# Adafruit_3_5in_480x320_FeatherWing.net
KiCad netlist of a schematic drawn in EAGLE
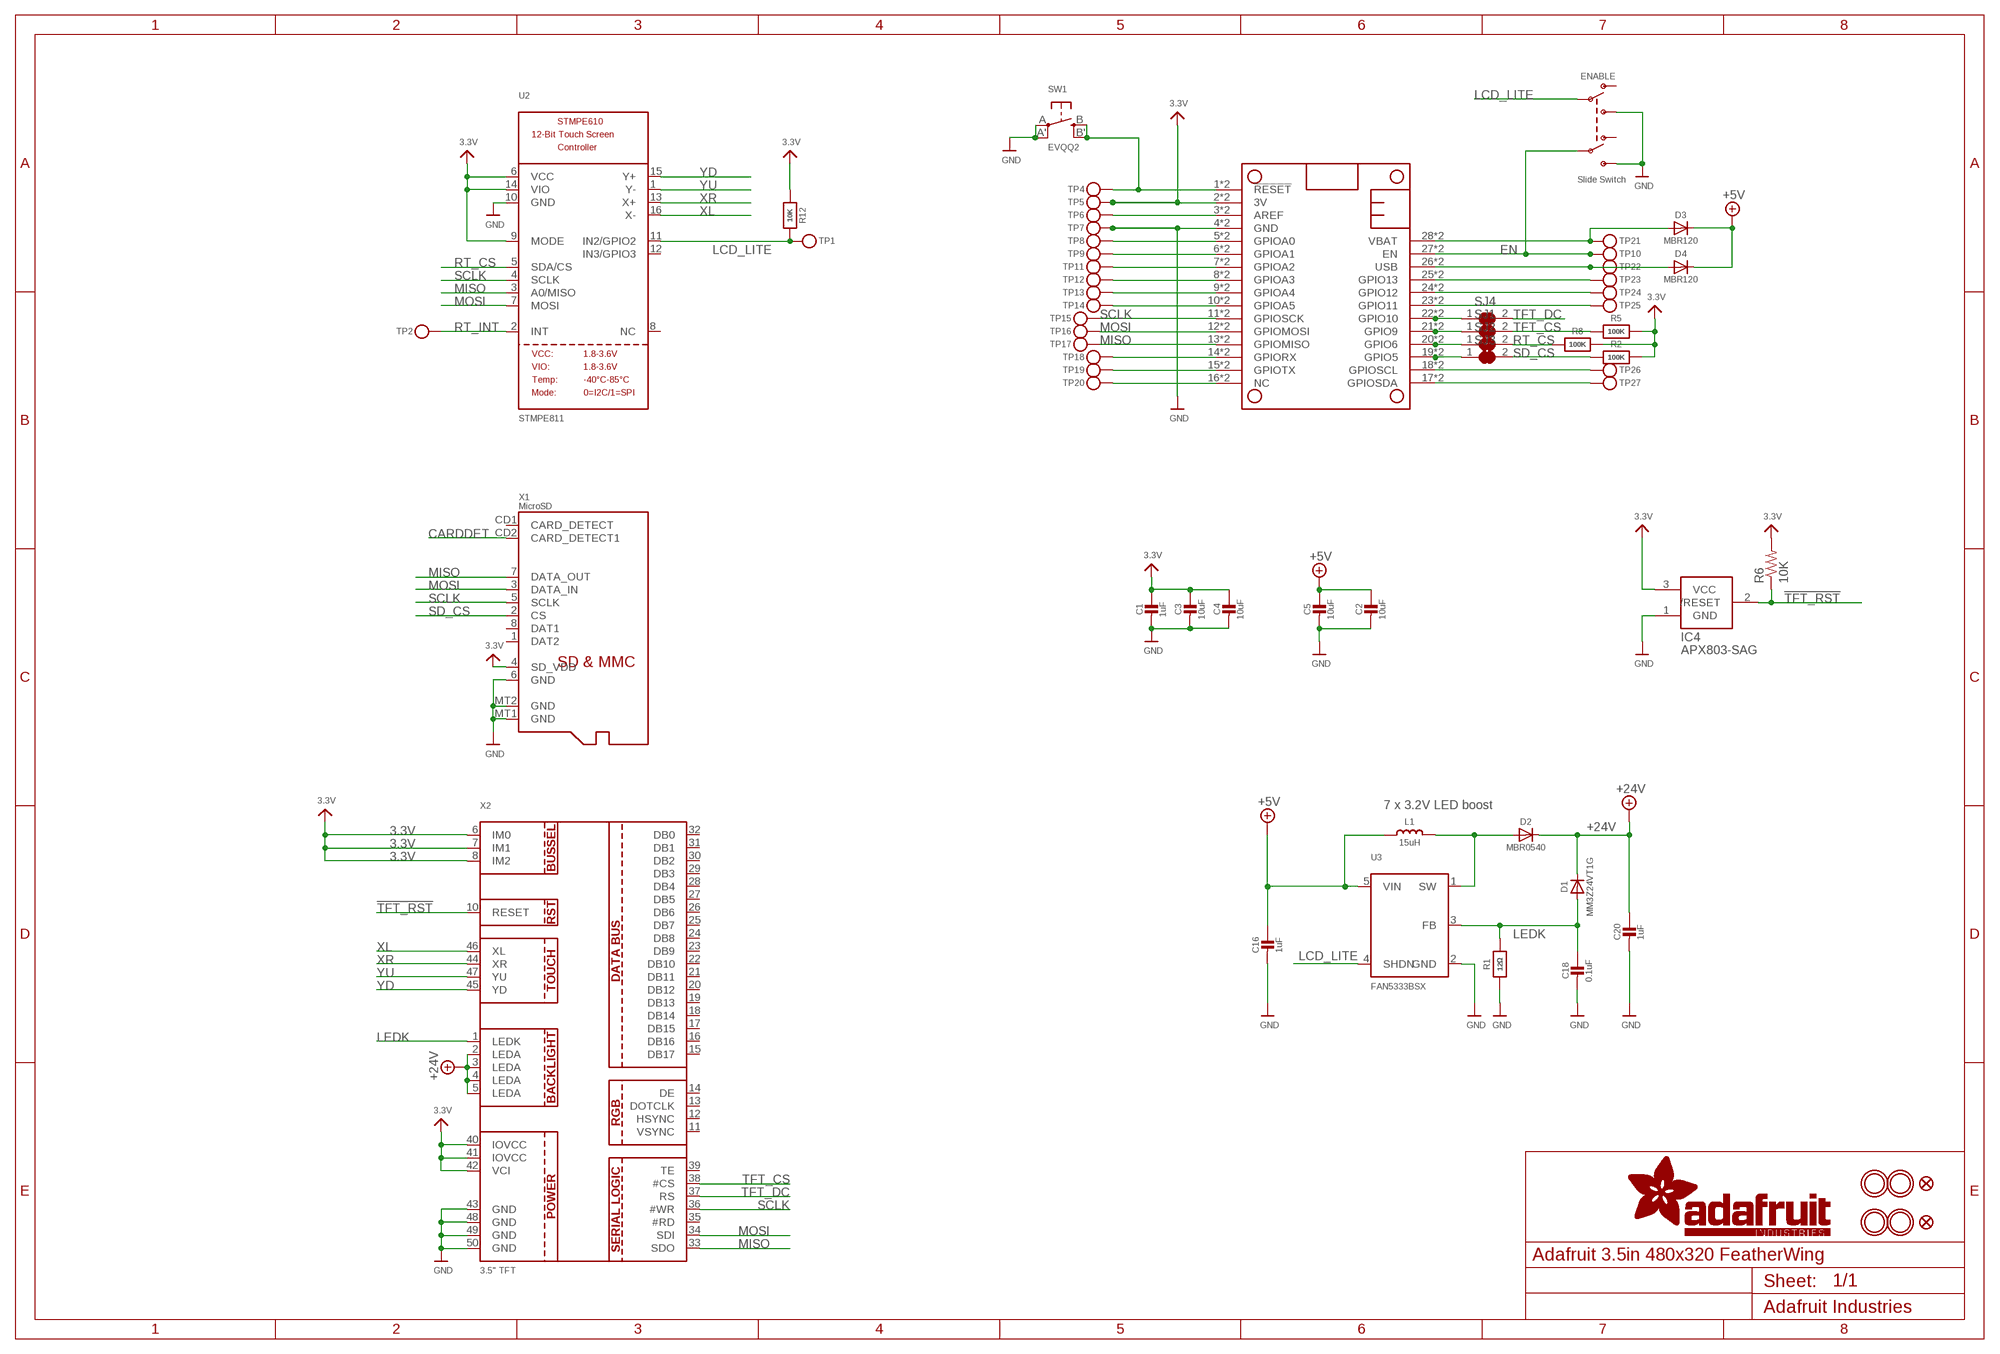
[diagram p0: schematic, sheet 1]

(export (version "E")
  (design (tool "Eeschema 10.0.6"))
  (components
    (comp (ref "C1")
      (value "1uF")
      (footprint "eagle-import:0805-NO")
      (libsource (lib "eagle-import") (part "CAP_CERAMIC0805-NOOUTLINE"))
    )
    (comp (ref "C2")
      (value "10uF")
      (footprint "eagle-import:0805-NO")
      (libsource (lib "eagle-import") (part "CAP_CERAMIC0805-NOOUTLINE"))
    )
    (comp (ref "C3")
      (value "10uF")
      (footprint "eagle-import:0805-NO")
      (libsource (lib "eagle-import") (part "CAP_CERAMIC0805-NOOUTLINE"))
    )
    (comp (ref "C4")
      (value "10uF")
      (footprint "eagle-import:0805-NO")
      (libsource (lib "eagle-import") (part "CAP_CERAMIC0805-NOOUTLINE"))
    )
    (comp (ref "C5")
      (value "10uF")
      (footprint "eagle-import:0805-NO")
      (libsource (lib "eagle-import") (part "CAP_CERAMIC0805-NOOUTLINE"))
    )
    (comp (ref "C16")
      (value "1uF")
      (footprint "eagle-import:0805-NO")
      (libsource (lib "eagle-import") (part "CAP_CERAMIC0805-NOOUTLINE"))
    )
    (comp (ref "C18")
      (value "0.1uF")
      (footprint "eagle-import:0805-NO")
      (libsource (lib "eagle-import") (part "CAP_CERAMIC0805-NOOUTLINE"))
    )
    (comp (ref "C20")
      (value "1uF")
      (footprint "eagle-import:0805-NO")
      (libsource (lib "eagle-import") (part "CAP_CERAMIC0805-NOOUTLINE"))
    )
    (comp (ref "D1")
      (value "MM3Z24VT1G")
      (footprint "eagle-import:SMADIODE")
      (libsource (lib "eagle-import") (part "DIODESMA"))
    )
    (comp (ref "D2")
      (value "MBR0540")
      (footprint "eagle-import:SOD-123")
      (libsource (lib "eagle-import") (part "DIODESOD-123"))
    )
    (comp (ref "D3")
      (value "MBR120")
      (footprint "eagle-import:SOD-123")
      (libsource (lib "eagle-import") (part "DIODESOD-123"))
    )
    (comp (ref "D4")
      (value "MBR120")
      (footprint "eagle-import:SOD-123")
      (libsource (lib "eagle-import") (part "DIODESOD-123"))
    )
    (comp (ref "ENABLE")
      (value "Slide Switch")
      (footprint "eagle-import:EG1390")
      (libsource (lib "eagle-import") (part "SWITCH_DPDTEG1390"))
    )
    (comp (ref "IC4")
      (value "APX803-SAG")
      (footprint "eagle-import:SOT23")
      (libsource (lib "eagle-import") (part "AXP083-SAG"))
    )
    (comp (ref "L1")
      (value "15uH")
      (footprint "eagle-import:INDUCTOR_5X5MM_NR5040_NOTHERMALS")
      (libsource (lib "eagle-import") (part "INDUCTORNR5040"))
    )
    (comp (ref "MS2")
      (value "FEATHERWING_SMTDUAL")
      (footprint "eagle-import:FEATHERWING_SMT2")
      (libsource (lib "eagle-import") (part "FEATHERWING_SMTDUAL"))
    )
    (comp (ref "R1")
      (value "12Ω")
      (footprint "eagle-import:0805-NO")
      (libsource (lib "eagle-import") (part "RESISTOR0805_NOOUTLINE"))
    )
    (comp (ref "R2")
      (value "100K")
      (footprint "eagle-import:0805-NO")
      (libsource (lib "eagle-import") (part "RESISTOR0805_NOOUTLINE"))
    )
    (comp (ref "R5")
      (value "100K")
      (footprint "eagle-import:0805-NO")
      (libsource (lib "eagle-import") (part "RESISTOR0805_NOOUTLINE"))
    )
    (comp (ref "R6")
      (value "10K")
      (footprint "eagle-import:R0805")
      (libsource (lib "eagle-import") (part "R-US_R0805"))
    )
    (comp (ref "R8")
      (value "100K")
      (footprint "eagle-import:0805-NO")
      (libsource (lib "eagle-import") (part "RESISTOR0805_NOOUTLINE"))
    )
    (comp (ref "R12")
      (value "10K")
      (footprint "eagle-import:0805-NO")
      (libsource (lib "eagle-import") (part "RESISTOR0805_NOOUTLINE"))
    )
    (comp (ref "SJ1")
      (value "SOLDERJUMPER_CLOSED")
      (footprint "eagle-import:SOLDERJUMPER_CLOSEDWIRE")
      (libsource (lib "eagle-import") (part "SOLDERJUMPER_CLOSED"))
    )
    (comp (ref "SJ2")
      (value "SOLDERJUMPER_CLOSED")
      (footprint "eagle-import:SOLDERJUMPER_CLOSEDWIRE")
      (libsource (lib "eagle-import") (part "SOLDERJUMPER_CLOSED"))
    )
    (comp (ref "SJ3")
      (value "SOLDERJUMPER_CLOSED")
      (footprint "eagle-import:SOLDERJUMPER_CLOSEDWIRE")
      (libsource (lib "eagle-import") (part "SOLDERJUMPER_CLOSED"))
    )
    (comp (ref "SJ4")
      (value "SOLDERJUMPER_CLOSED")
      (footprint "eagle-import:SOLDERJUMPER_CLOSEDWIRE")
      (libsource (lib "eagle-import") (part "SOLDERJUMPER_CLOSED"))
    )
    (comp (ref "SW1")
      (value "EVQQ2")
      (footprint "eagle-import:EVQ-Q2_SMALLER")
      (libsource (lib "eagle-import") (part "SWITCH_TACT_SMT_EVQQ2_SMALL"))
    )
    (comp (ref "TP1")
      (value "TESTPOINTPAD2MM")
      (footprint "eagle-import:TESTPOINT_PAD_2MM")
      (libsource (lib "eagle-import") (part "TESTPOINTPAD2MM"))
    )
    (comp (ref "TP2")
      (value "TESTPOINTPAD2MM")
      (footprint "eagle-import:TESTPOINT_PAD_2MM")
      (libsource (lib "eagle-import") (part "TESTPOINTPAD2MM"))
    )
    (comp (ref "TP4")
      (value "TESTPOINTPAD2MM")
      (footprint "eagle-import:TESTPOINT_PAD_2MM")
      (libsource (lib "eagle-import") (part "TESTPOINTPAD2MM"))
    )
    (comp (ref "TP5")
      (value "TESTPOINTPAD2MM")
      (footprint "eagle-import:TESTPOINT_PAD_2MM")
      (libsource (lib "eagle-import") (part "TESTPOINTPAD2MM"))
    )
    (comp (ref "TP6")
      (value "TESTPOINTPAD2MM")
      (footprint "eagle-import:TESTPOINT_PAD_2MM")
      (libsource (lib "eagle-import") (part "TESTPOINTPAD2MM"))
    )
    (comp (ref "TP7")
      (value "TESTPOINTPAD2MM")
      (footprint "eagle-import:TESTPOINT_PAD_2MM")
      (libsource (lib "eagle-import") (part "TESTPOINTPAD2MM"))
    )
    (comp (ref "TP8")
      (value "TESTPOINTPAD2MM")
      (footprint "eagle-import:TESTPOINT_PAD_2MM")
      (libsource (lib "eagle-import") (part "TESTPOINTPAD2MM"))
    )
    (comp (ref "TP9")
      (value "TESTPOINTPAD2MM")
      (footprint "eagle-import:TESTPOINT_PAD_2MM")
      (libsource (lib "eagle-import") (part "TESTPOINTPAD2MM"))
    )
    (comp (ref "TP10")
      (value "TESTPOINTPAD2MM")
      (footprint "eagle-import:TESTPOINT_PAD_2MM")
      (libsource (lib "eagle-import") (part "TESTPOINTPAD2MM"))
    )
    (comp (ref "TP11")
      (value "TESTPOINTPAD2MM")
      (footprint "eagle-import:TESTPOINT_PAD_2MM")
      (libsource (lib "eagle-import") (part "TESTPOINTPAD2MM"))
    )
    (comp (ref "TP12")
      (value "TESTPOINTPAD2MM")
      (footprint "eagle-import:TESTPOINT_PAD_2MM")
      (libsource (lib "eagle-import") (part "TESTPOINTPAD2MM"))
    )
    (comp (ref "TP13")
      (value "TESTPOINTPAD2MM")
      (footprint "eagle-import:TESTPOINT_PAD_2MM")
      (libsource (lib "eagle-import") (part "TESTPOINTPAD2MM"))
    )
    (comp (ref "TP14")
      (value "TESTPOINTPAD2MM")
      (footprint "eagle-import:TESTPOINT_PAD_2MM")
      (libsource (lib "eagle-import") (part "TESTPOINTPAD2MM"))
    )
    (comp (ref "TP15")
      (value "TESTPOINTPAD2MM")
      (footprint "eagle-import:TESTPOINT_PAD_2MM")
      (libsource (lib "eagle-import") (part "TESTPOINTPAD2MM"))
    )
    (comp (ref "TP16")
      (value "TESTPOINTPAD2MM")
      (footprint "eagle-import:TESTPOINT_PAD_2MM")
      (libsource (lib "eagle-import") (part "TESTPOINTPAD2MM"))
    )
    (comp (ref "TP17")
      (value "TESTPOINTPAD2MM")
      (footprint "eagle-import:TESTPOINT_PAD_2MM")
      (libsource (lib "eagle-import") (part "TESTPOINTPAD2MM"))
    )
    (comp (ref "TP18")
      (value "TESTPOINTPAD2MM")
      (footprint "eagle-import:TESTPOINT_PAD_2MM")
      (libsource (lib "eagle-import") (part "TESTPOINTPAD2MM"))
    )
    (comp (ref "TP19")
      (value "TESTPOINTPAD2MM")
      (footprint "eagle-import:TESTPOINT_PAD_2MM")
      (libsource (lib "eagle-import") (part "TESTPOINTPAD2MM"))
    )
    (comp (ref "TP20")
      (value "TESTPOINTPAD2MM")
      (footprint "eagle-import:TESTPOINT_PAD_2MM")
      (libsource (lib "eagle-import") (part "TESTPOINTPAD2MM"))
    )
    (comp (ref "TP21")
      (value "TESTPOINTPAD2MM")
      (footprint "eagle-import:TESTPOINT_PAD_2MM")
      (libsource (lib "eagle-import") (part "TESTPOINTPAD2MM"))
    )
    (comp (ref "TP22")
      (value "TESTPOINTPAD2MM")
      (footprint "eagle-import:TESTPOINT_PAD_2MM")
      (libsource (lib "eagle-import") (part "TESTPOINTPAD2MM"))
    )
    (comp (ref "TP23")
      (value "TESTPOINTPAD2MM")
      (footprint "eagle-import:TESTPOINT_PAD_2MM")
      (libsource (lib "eagle-import") (part "TESTPOINTPAD2MM"))
    )
    (comp (ref "TP24")
      (value "TESTPOINTPAD2MM")
      (footprint "eagle-import:TESTPOINT_PAD_2MM")
      (libsource (lib "eagle-import") (part "TESTPOINTPAD2MM"))
    )
    (comp (ref "TP25")
      (value "TESTPOINTPAD2MM")
      (footprint "eagle-import:TESTPOINT_PAD_2MM")
      (libsource (lib "eagle-import") (part "TESTPOINTPAD2MM"))
    )
    (comp (ref "TP26")
      (value "TESTPOINTPAD2MM")
      (footprint "eagle-import:TESTPOINT_PAD_2MM")
      (libsource (lib "eagle-import") (part "TESTPOINTPAD2MM"))
    )
    (comp (ref "TP27")
      (value "TESTPOINTPAD2MM")
      (footprint "eagle-import:TESTPOINT_PAD_2MM")
      (libsource (lib "eagle-import") (part "TESTPOINTPAD2MM"))
    )
    (comp (ref "U$7")
      (value "MOUNTINGHOLE3.0THIN")
      (footprint "eagle-import:MOUNTINGHOLE_3.0_PLATEDTHIN")
      (libsource (lib "eagle-import") (part "MOUNTINGHOLE3.0THIN"))
    )
    (comp (ref "U$9")
      (value "FIDUCIAL_1MM")
      (footprint "eagle-import:FIDUCIAL_1MM")
      (libsource (lib "eagle-import") (part "FIDUCIAL_1MM"))
    )
    (comp (ref "U$15")
      (value "MOUNTINGHOLE3.0THIN")
      (footprint "eagle-import:MOUNTINGHOLE_3.0_PLATEDTHIN")
      (libsource (lib "eagle-import") (part "MOUNTINGHOLE3.0THIN"))
    )
    (comp (ref "U$16")
      (value "MOUNTINGHOLE3.0THIN")
      (footprint "eagle-import:MOUNTINGHOLE_3.0_PLATEDTHIN")
      (libsource (lib "eagle-import") (part "MOUNTINGHOLE3.0THIN"))
    )
    (comp (ref "U$17")
      (value "MOUNTINGHOLE3.0THIN")
      (footprint "eagle-import:MOUNTINGHOLE_3.0_PLATEDTHIN")
      (libsource (lib "eagle-import") (part "MOUNTINGHOLE3.0THIN"))
    )
    (comp (ref "U$23")
      (value "FIDUCIAL_1MM")
      (footprint "eagle-import:FIDUCIAL_1MM")
      (libsource (lib "eagle-import") (part "FIDUCIAL_1MM"))
    )
    (comp (ref "U2")
      (value "STMPE811")
      (footprint "eagle-import:QFN16_3MM")
      (libsource (lib "eagle-import") (part "STMPE610"))
    )
    (comp (ref "U3")
      (value "FAN5333BSX")
      (footprint "eagle-import:SOT23-5@1")
      (libsource (lib "eagle-import") (part "FAN5331"))
    )
    (comp (ref "X1")
      (value "MicroSD")
      (footprint "eagle-import:MICROSD")
      (libsource (lib "eagle-import") (part "MICROSD"))
    )
    (comp (ref "X2")
      (value "3.5\" TFT")
      (footprint "eagle-import:TFT_3.5IN_320X480_50PIN")
      (libsource (lib "eagle-import") (part "DISP_LCD_3.5IN_320X480_50PIN"))
    )
  )
  (nets
    (net (code "1") (name "+5V") (class "Default")
      (node (ref "C16") (pin "1") (pinfunction "1_1") (pintype "passive"))
      (node (ref "C2") (pin "1") (pinfunction "1_1") (pintype "passive"))
      (node (ref "C5") (pin "1") (pinfunction "1_1") (pintype "passive"))
      (node (ref "D3") (pin "C") (pinfunction "C_C") (pintype "passive"))
      (node (ref "D4") (pin "C") (pinfunction "C_C") (pintype "passive"))
      (node (ref "L1") (pin "P$1") (pinfunction "1_P$1") (pintype "passive"))
      (node (ref "U3") (pin "5") (pinfunction "VIN_5") (pintype "bidirectional"))
    )
    (net (code "2") (name "+24V") (class "Default")
      (node (ref "C20") (pin "1") (pinfunction "1_1") (pintype "passive"))
      (node (ref "D1") (pin "C") (pinfunction "C_C") (pintype "passive"))
      (node (ref "D2") (pin "C") (pinfunction "C_C") (pintype "passive"))
      (node (ref "X2") (pin "2") (pinfunction "LEDA_2") (pintype "bidirectional"))
      (node (ref "X2") (pin "3") (pinfunction "LEDA_3") (pintype "bidirectional"))
      (node (ref "X2") (pin "4") (pinfunction "LEDA_4") (pintype "bidirectional"))
      (node (ref "X2") (pin "5") (pinfunction "LEDA_5") (pintype "bidirectional"))
    )
    (net (code "3") (name "/CARDDET") (class "Default")
      (node (ref "X1") (pin "CD2") (pinfunction "CARD_DETECT1_CD2") (pintype "passive"))
    )
    (net (code "4") (name "/EN") (class "Default")
      (node (ref "ENABLE") (pin "P2") (pinfunction "P2_P2") (pintype "passive"))
      (node (ref "MS2") (pin "27") (pinfunction "EN_27") (pintype "passive"))
      (node (ref "MS2") (pin "27'") (pinfunction "EN_27'") (pintype "passive"))
      (node (ref "TP10") (pin "P$1") (pinfunction "P$1_P$1") (pintype "bidirectional"))
    )
    (net (code "5") (name "/LCD_LITE") (class "Default")
      (node (ref "ENABLE") (pin "P1") (pinfunction "P1_P1") (pintype "passive"))
      (node (ref "R12") (pin "2") (pinfunction "2_2") (pintype "passive"))
      (node (ref "TP1") (pin "P$1") (pinfunction "P$1_P$1") (pintype "bidirectional"))
      (node (ref "U2") (pin "11") (pinfunction "IN2/GPIO2_11") (pintype "bidirectional"))
      (node (ref "U3") (pin "4") (pinfunction "SHDN_4") (pintype "bidirectional"))
    )
    (net (code "6") (name "/LEDK") (class "Default")
      (node (ref "C18") (pin "1") (pinfunction "1_1") (pintype "passive"))
      (node (ref "D1") (pin "A") (pinfunction "A_A") (pintype "passive"))
      (node (ref "R1") (pin "2") (pinfunction "2_2") (pintype "passive"))
      (node (ref "U3") (pin "3") (pinfunction "FB_3") (pintype "bidirectional"))
      (node (ref "X2") (pin "1") (pinfunction "LEDK_1") (pintype "bidirectional"))
    )
    (net (code "7") (name "/MISO") (class "Default")
      (node (ref "MS2") (pin "13") (pinfunction "GPIOMISO_13") (pintype "bidirectional"))
      (node (ref "MS2") (pin "13'") (pinfunction "GPIOMISO_13'") (pintype "bidirectional"))
      (node (ref "TP17") (pin "P$1") (pinfunction "P$1_P$1") (pintype "bidirectional"))
      (node (ref "U2") (pin "3") (pinfunction "A0/MISO_3") (pintype "bidirectional"))
      (node (ref "X1") (pin "7") (pinfunction "DATA_OUT_7") (pintype "output"))
      (node (ref "X2") (pin "33") (pinfunction "SDO_33") (pintype "bidirectional"))
    )
    (net (code "8") (name "/MOSI") (class "Default")
      (node (ref "MS2") (pin "12") (pinfunction "GPIOMOSI_12") (pintype "bidirectional"))
      (node (ref "MS2") (pin "12'") (pinfunction "GPIOMOSI_12'") (pintype "bidirectional"))
      (node (ref "TP16") (pin "P$1") (pinfunction "P$1_P$1") (pintype "bidirectional"))
      (node (ref "U2") (pin "7") (pinfunction "MOSI_7") (pintype "input"))
      (node (ref "X1") (pin "3") (pinfunction "DATA_IN_3") (pintype "input"))
      (node (ref "X2") (pin "34") (pinfunction "SDI_34") (pintype "bidirectional"))
    )
    (net (code "9") (name "/RT_CS") (class "Default")
      (node (ref "R8") (pin "1") (pinfunction "1_1") (pintype "passive"))
      (node (ref "SJ2") (pin "2") (pinfunction "2_2") (pintype "passive"))
      (node (ref "U2") (pin "5") (pinfunction "SDA/CS_5") (pintype "bidirectional"))
    )
    (net (code "10") (name "/RT_INT") (class "Default")
      (node (ref "TP2") (pin "P$1") (pinfunction "P$1_P$1") (pintype "bidirectional"))
      (node (ref "U2") (pin "2") (pinfunction "INT_2") (pintype "output"))
    )
    (net (code "11") (name "/SCLK") (class "Default")
      (node (ref "MS2") (pin "11") (pinfunction "GPIOSCK_11") (pintype "bidirectional"))
      (node (ref "MS2") (pin "11'") (pinfunction "GPIOSCK_11'") (pintype "bidirectional"))
      (node (ref "TP15") (pin "P$1") (pinfunction "P$1_P$1") (pintype "bidirectional"))
      (node (ref "U2") (pin "4") (pinfunction "SCLK_4") (pintype "bidirectional"))
      (node (ref "X1") (pin "5") (pinfunction "SCLK_5") (pintype "input"))
      (node (ref "X2") (pin "36") (pinfunction "#WR_36") (pintype "bidirectional"))
    )
    (net (code "12") (name "/SD_CS") (class "Default")
      (node (ref "R2") (pin "1") (pinfunction "1_1") (pintype "passive"))
      (node (ref "SJ3") (pin "2") (pinfunction "2_2") (pintype "passive"))
      (node (ref "X1") (pin "2") (pinfunction "CS_2") (pintype "input"))
    )
    (net (code "13") (name "/TFT_CS") (class "Default")
      (node (ref "R5") (pin "1") (pinfunction "1_1") (pintype "passive"))
      (node (ref "SJ1") (pin "2") (pinfunction "2_2") (pintype "passive"))
      (node (ref "X2") (pin "38") (pinfunction "#CS_38") (pintype "bidirectional"))
    )
    (net (code "14") (name "/TFT_DC") (class "Default")
      (node (ref "SJ4") (pin "2") (pinfunction "2_2") (pintype "passive"))
      (node (ref "X2") (pin "37") (pinfunction "RS_37") (pintype "bidirectional"))
    )
    (net (code "15") (name "/XL") (class "Default")
      (node (ref "U2") (pin "16") (pinfunction "X-_16") (pintype "input"))
      (node (ref "X2") (pin "46") (pinfunction "XL_46") (pintype "bidirectional"))
    )
    (net (code "16") (name "/XR") (class "Default")
      (node (ref "U2") (pin "13") (pinfunction "X+_13") (pintype "input"))
      (node (ref "X2") (pin "44") (pinfunction "XR_44") (pintype "bidirectional"))
    )
    (net (code "17") (name "/YD") (class "Default")
      (node (ref "U2") (pin "15") (pinfunction "Y+_15") (pintype "input"))
      (node (ref "X2") (pin "45") (pinfunction "YD_45") (pintype "bidirectional"))
    )
    (net (code "18") (name "/YU") (class "Default")
      (node (ref "U2") (pin "1") (pinfunction "Y-_1") (pintype "input"))
      (node (ref "X2") (pin "47") (pinfunction "YU_47") (pintype "bidirectional"))
    )
    (net (code "19") (name "/~{TFT_RST}") (class "Default")
      (node (ref "IC4") (pin "2") (pinfunction "/RESET_2") (pintype "output"))
      (node (ref "R6") (pin "1") (pinfunction "1_1") (pintype "passive"))
      (node (ref "X2") (pin "10") (pinfunction "RESET_10") (pintype "bidirectional"))
    )
    (net (code "20") (name "3.3V") (class "Default")
      (node (ref "C1") (pin "1") (pinfunction "1_1") (pintype "passive"))
      (node (ref "C3") (pin "1") (pinfunction "1_1") (pintype "passive"))
      (node (ref "C4") (pin "1") (pinfunction "1_1") (pintype "passive"))
      (node (ref "IC4") (pin "3") (pinfunction "VCC_3") (pintype "power_in"))
      (node (ref "MS2") (pin "2") (pinfunction "3V_2") (pintype "power_in"))
      (node (ref "MS2") (pin "2'") (pinfunction "3V_2'") (pintype "power_in"))
      (node (ref "R12") (pin "1") (pinfunction "1_1") (pintype "passive"))
      (node (ref "R2") (pin "2") (pinfunction "2_2") (pintype "passive"))
      (node (ref "R5") (pin "2") (pinfunction "2_2") (pintype "passive"))
      (node (ref "R6") (pin "2") (pinfunction "2_2") (pintype "passive"))
      (node (ref "R8") (pin "2") (pinfunction "2_2") (pintype "passive"))
      (node (ref "TP5") (pin "P$1") (pinfunction "P$1_P$1") (pintype "bidirectional"))
      (node (ref "U2") (pin "14") (pinfunction "VIO_14") (pintype "power_in"))
      (node (ref "U2") (pin "6") (pinfunction "VCC_6") (pintype "power_in"))
      (node (ref "U2") (pin "9") (pinfunction "MODE_9") (pintype "input"))
      (node (ref "X1") (pin "4") (pinfunction "SD_VDD_4") (pintype "power_in"))
      (node (ref "X2") (pin "40") (pinfunction "IOVCC_40") (pintype "bidirectional"))
      (node (ref "X2") (pin "41") (pinfunction "IOVCC_41") (pintype "bidirectional"))
      (node (ref "X2") (pin "42") (pinfunction "VCI_42") (pintype "bidirectional"))
      (node (ref "X2") (pin "6") (pinfunction "IM0_6") (pintype "bidirectional"))
      (node (ref "X2") (pin "7") (pinfunction "IM1_7") (pintype "bidirectional"))
      (node (ref "X2") (pin "8") (pinfunction "IM2_8") (pintype "bidirectional"))
    )
    (net (code "21") (name "GND") (class "Default")
      (node (ref "C1") (pin "2") (pinfunction "2_2") (pintype "passive"))
      (node (ref "C16") (pin "2") (pinfunction "2_2") (pintype "passive"))
      (node (ref "C18") (pin "2") (pinfunction "2_2") (pintype "passive"))
      (node (ref "C2") (pin "2") (pinfunction "2_2") (pintype "passive"))
      (node (ref "C20") (pin "2") (pinfunction "2_2") (pintype "passive"))
      (node (ref "C3") (pin "2") (pinfunction "2_2") (pintype "passive"))
      (node (ref "C4") (pin "2") (pinfunction "2_2") (pintype "passive"))
      (node (ref "C5") (pin "2") (pinfunction "2_2") (pintype "passive"))
      (node (ref "ENABLE") (pin "S1") (pinfunction "S1_S1") (pintype "passive"))
      (node (ref "ENABLE") (pin "S2") (pinfunction "S2_S2") (pintype "passive"))
      (node (ref "IC4") (pin "1") (pinfunction "GND_1") (pintype "power_in"))
      (node (ref "MS2") (pin "4") (pinfunction "GND_4") (pintype "power_in"))
      (node (ref "MS2") (pin "4'") (pinfunction "GND_4'") (pintype "power_in"))
      (node (ref "R1") (pin "1") (pinfunction "1_1") (pintype "passive"))
      (node (ref "SW1") (pin "A") (pinfunction "P_A") (pintype "passive"))
      (node (ref "SW1") (pin "A'") (pinfunction "P1_A'") (pintype "passive"))
      (node (ref "TP7") (pin "P$1") (pinfunction "P$1_P$1") (pintype "bidirectional"))
      (node (ref "U2") (pin "10") (pinfunction "GND_10") (pintype "power_in"))
      (node (ref "U3") (pin "2") (pinfunction "GND_2") (pintype "bidirectional"))
      (node (ref "X1") (pin "6") (pinfunction "GND_6") (pintype "power_in"))
      (node (ref "X1") (pin "MT1") (pinfunction "GND_MT1") (pintype "power_in"))
      (node (ref "X1") (pin "MT2") (pinfunction "GND_MT2") (pintype "power_in"))
      (node (ref "X2") (pin "43") (pinfunction "GND_43") (pintype "bidirectional"))
      (node (ref "X2") (pin "48") (pinfunction "GND_48") (pintype "bidirectional"))
      (node (ref "X2") (pin "49") (pinfunction "GND_49") (pintype "bidirectional"))
      (node (ref "X2") (pin "50") (pinfunction "GND_50") (pintype "bidirectional"))
    )
    (net (code "22") (name "Net-(D3-PadA)") (class "Default")
      (node (ref "D3") (pin "A") (pinfunction "A_A") (pintype "passive"))
      (node (ref "MS2") (pin "28") (pinfunction "VBAT_28") (pintype "power_in"))
      (node (ref "MS2") (pin "28'") (pinfunction "VBAT_28'") (pintype "power_in"))
      (node (ref "TP21") (pin "P$1") (pinfunction "P$1_P$1") (pintype "bidirectional"))
    )
    (net (code "23") (name "Net-(D4-PadA)") (class "Default")
      (node (ref "D4") (pin "A") (pinfunction "A_A") (pintype "passive"))
      (node (ref "MS2") (pin "26") (pinfunction "USB_26") (pintype "power_in"))
      (node (ref "MS2") (pin "26'") (pinfunction "USB_26'") (pintype "power_in"))
      (node (ref "TP22") (pin "P$1") (pinfunction "P$1_P$1") (pintype "bidirectional"))
    )
    (net (code "24") (name "Net-(L1-2)") (class "Default")
      (node (ref "D2") (pin "A") (pinfunction "A_A") (pintype "passive"))
      (node (ref "L1") (pin "P$2") (pinfunction "2_P$2") (pintype "passive"))
      (node (ref "U3") (pin "1") (pinfunction "SW_1") (pintype "bidirectional"))
    )
    (net (code "25") (name "Net-(MS2-AREF-Pad3')") (class "Default")
      (node (ref "MS2") (pin "3") (pinfunction "AREF_3") (pintype "passive"))
      (node (ref "MS2") (pin "3'") (pinfunction "AREF_3'") (pintype "passive"))
      (node (ref "TP6") (pin "P$1") (pinfunction "P$1_P$1") (pintype "bidirectional"))
    )
    (net (code "26") (name "Net-(MS2-GPIO5-Pad19')") (class "Default")
      (node (ref "MS2") (pin "19") (pinfunction "GPIO5_19") (pintype "bidirectional"))
      (node (ref "MS2") (pin "19'") (pinfunction "GPIO5_19'") (pintype "bidirectional"))
      (node (ref "SJ3") (pin "1") (pinfunction "1_1") (pintype "passive"))
    )
    (net (code "27") (name "Net-(MS2-GPIO6-Pad20')") (class "Default")
      (node (ref "MS2") (pin "20") (pinfunction "GPIO6_20") (pintype "bidirectional"))
      (node (ref "MS2") (pin "20'") (pinfunction "GPIO6_20'") (pintype "bidirectional"))
      (node (ref "SJ2") (pin "1") (pinfunction "1_1") (pintype "passive"))
    )
    (net (code "28") (name "Net-(MS2-GPIO9-Pad21')") (class "Default")
      (node (ref "MS2") (pin "21") (pinfunction "GPIO9_21") (pintype "bidirectional"))
      (node (ref "MS2") (pin "21'") (pinfunction "GPIO9_21'") (pintype "bidirectional"))
      (node (ref "SJ1") (pin "1") (pinfunction "1_1") (pintype "passive"))
    )
    (net (code "29") (name "Net-(MS2-GPIO10-Pad22')") (class "Default")
      (node (ref "MS2") (pin "22") (pinfunction "GPIO10_22") (pintype "bidirectional"))
      (node (ref "MS2") (pin "22'") (pinfunction "GPIO10_22'") (pintype "bidirectional"))
      (node (ref "SJ4") (pin "1") (pinfunction "1_1") (pintype "passive"))
    )
    (net (code "30") (name "Net-(MS2-GPIO11-Pad23')") (class "Default")
      (node (ref "MS2") (pin "23") (pinfunction "GPIO11_23") (pintype "bidirectional"))
      (node (ref "MS2") (pin "23'") (pinfunction "GPIO11_23'") (pintype "bidirectional"))
      (node (ref "TP25") (pin "P$1") (pinfunction "P$1_P$1") (pintype "bidirectional"))
    )
    (net (code "31") (name "Net-(MS2-GPIO12-Pad24')") (class "Default")
      (node (ref "MS2") (pin "24") (pinfunction "GPIO12_24") (pintype "bidirectional"))
      (node (ref "MS2") (pin "24'") (pinfunction "GPIO12_24'") (pintype "bidirectional"))
      (node (ref "TP24") (pin "P$1") (pinfunction "P$1_P$1") (pintype "bidirectional"))
    )
    (net (code "32") (name "Net-(MS2-GPIO13-Pad25')") (class "Default")
      (node (ref "MS2") (pin "25") (pinfunction "GPIO13_25") (pintype "bidirectional"))
      (node (ref "MS2") (pin "25'") (pinfunction "GPIO13_25'") (pintype "bidirectional"))
      (node (ref "TP23") (pin "P$1") (pinfunction "P$1_P$1") (pintype "bidirectional"))
    )
    (net (code "33") (name "Net-(MS2-GPIOA0-Pad5')") (class "Default")
      (node (ref "MS2") (pin "5") (pinfunction "GPIOA0_5") (pintype "bidirectional"))
      (node (ref "MS2") (pin "5'") (pinfunction "GPIOA0_5'") (pintype "bidirectional"))
      (node (ref "TP8") (pin "P$1") (pinfunction "P$1_P$1") (pintype "bidirectional"))
    )
    (net (code "34") (name "Net-(MS2-GPIOA1-Pad6')") (class "Default")
      (node (ref "MS2") (pin "6") (pinfunction "GPIOA1_6") (pintype "bidirectional"))
      (node (ref "MS2") (pin "6'") (pinfunction "GPIOA1_6'") (pintype "bidirectional"))
      (node (ref "TP9") (pin "P$1") (pinfunction "P$1_P$1") (pintype "bidirectional"))
    )
    (net (code "35") (name "Net-(MS2-GPIOA2-Pad7')") (class "Default")
      (node (ref "MS2") (pin "7") (pinfunction "GPIOA2_7") (pintype "bidirectional"))
      (node (ref "MS2") (pin "7'") (pinfunction "GPIOA2_7'") (pintype "bidirectional"))
      (node (ref "TP11") (pin "P$1") (pinfunction "P$1_P$1") (pintype "bidirectional"))
    )
    (net (code "36") (name "Net-(MS2-GPIOA3-Pad8')") (class "Default")
      (node (ref "MS2") (pin "8") (pinfunction "GPIOA3_8") (pintype "bidirectional"))
      (node (ref "MS2") (pin "8'") (pinfunction "GPIOA3_8'") (pintype "bidirectional"))
      (node (ref "TP12") (pin "P$1") (pinfunction "P$1_P$1") (pintype "bidirectional"))
    )
    (net (code "37") (name "Net-(MS2-GPIOA4-Pad9')") (class "Default")
      (node (ref "MS2") (pin "9") (pinfunction "GPIOA4_9") (pintype "bidirectional"))
      (node (ref "MS2") (pin "9'") (pinfunction "GPIOA4_9'") (pintype "bidirectional"))
      (node (ref "TP13") (pin "P$1") (pinfunction "P$1_P$1") (pintype "bidirectional"))
    )
    (net (code "38") (name "Net-(MS2-GPIOA5-Pad10')") (class "Default")
      (node (ref "MS2") (pin "10") (pinfunction "GPIOA5_10") (pintype "bidirectional"))
      (node (ref "MS2") (pin "10'") (pinfunction "GPIOA5_10'") (pintype "bidirectional"))
      (node (ref "TP14") (pin "P$1") (pinfunction "P$1_P$1") (pintype "bidirectional"))
    )
    (net (code "39") (name "Net-(MS2-GPIORX-Pad14')") (class "Default")
      (node (ref "MS2") (pin "14") (pinfunction "GPIORX_14") (pintype "bidirectional"))
      (node (ref "MS2") (pin "14'") (pinfunction "GPIORX_14'") (pintype "bidirectional"))
      (node (ref "TP18") (pin "P$1") (pinfunction "P$1_P$1") (pintype "bidirectional"))
    )
    (net (code "40") (name "Net-(MS2-GPIOSCL-Pad18')") (class "Default")
      (node (ref "MS2") (pin "18") (pinfunction "GPIOSCL_18") (pintype "bidirectional"))
      (node (ref "MS2") (pin "18'") (pinfunction "GPIOSCL_18'") (pintype "bidirectional"))
      (node (ref "TP26") (pin "P$1") (pinfunction "P$1_P$1") (pintype "bidirectional"))
    )
    (net (code "41") (name "Net-(MS2-GPIOSDA-Pad17')") (class "Default")
      (node (ref "MS2") (pin "17") (pinfunction "GPIOSDA_17") (pintype "bidirectional"))
      (node (ref "MS2") (pin "17'") (pinfunction "GPIOSDA_17'") (pintype "bidirectional"))
      (node (ref "TP27") (pin "P$1") (pinfunction "P$1_P$1") (pintype "bidirectional"))
    )
    (net (code "42") (name "Net-(MS2-GPIOTX-Pad15')") (class "Default")
      (node (ref "MS2") (pin "15") (pinfunction "GPIOTX_15") (pintype "bidirectional"))
      (node (ref "MS2") (pin "15'") (pinfunction "GPIOTX_15'") (pintype "bidirectional"))
      (node (ref "TP19") (pin "P$1") (pinfunction "P$1_P$1") (pintype "bidirectional"))
    )
    (net (code "43") (name "Net-(MS2-NC-Pad16')") (class "Default")
      (node (ref "MS2") (pin "16") (pinfunction "NC_16") (pintype "passive"))
      (node (ref "MS2") (pin "16'") (pinfunction "NC_16'") (pintype "passive"))
      (node (ref "TP20") (pin "P$1") (pinfunction "P$1_P$1") (pintype "bidirectional"))
    )
    (net (code "44") (name "Net-(SW1-S)") (class "Default")
      (node (ref "MS2") (pin "1") (pinfunction "~{RESET}_1") (pintype "input"))
      (node (ref "MS2") (pin "1'") (pinfunction "~{RESET}_1'") (pintype "input"))
      (node (ref "SW1") (pin "B") (pinfunction "S_B") (pintype "passive"))
      (node (ref "SW1") (pin "B'") (pinfunction "S1_B'") (pintype "passive"))
      (node (ref "TP4") (pin "P$1") (pinfunction "P$1_P$1") (pintype "bidirectional"))
    )
    (net (code "45") (name "unconnected-(ENABLE-PadO1)") (class "Default")
      (node (ref "ENABLE") (pin "O1") (pinfunction "O1_O1") (pintype "passive"))
    )
    (net (code "46") (name "unconnected-(ENABLE-PadO2)") (class "Default")
      (node (ref "ENABLE") (pin "O2") (pinfunction "O2_O2") (pintype "passive"))
    )
    (net (code "47") (name "unconnected-(U2-IN3{slash}GPIO3-Pad12)") (class "Default")
      (node (ref "U2") (pin "12") (pinfunction "IN3/GPIO3_12") (pintype "bidirectional"))
    )
    (net (code "48") (name "unconnected-(U2-NC-Pad8)") (class "Default")
      (node (ref "U2") (pin "8") (pinfunction "NC_8") (pintype "no_connect"))
    )
    (net (code "49") (name "unconnected-(X1-CARD_DETECT-PadCD1)") (class "Default")
      (node (ref "X1") (pin "CD1") (pinfunction "CARD_DETECT_CD1") (pintype "passive"))
    )
    (net (code "50") (name "unconnected-(X1-DAT1-Pad8)") (class "Default")
      (node (ref "X1") (pin "8") (pinfunction "DAT1_8") (pintype "bidirectional"))
    )
    (net (code "51") (name "unconnected-(X1-DAT2-Pad1)") (class "Default")
      (node (ref "X1") (pin "1") (pinfunction "DAT2_1") (pintype "bidirectional"))
    )
    (net (code "52") (name "unconnected-(X2-#RD-Pad35)") (class "Default")
      (node (ref "X2") (pin "35") (pinfunction "#RD_35") (pintype "bidirectional"))
    )
    (net (code "53") (name "unconnected-(X2-DB0-Pad32)") (class "Default")
      (node (ref "X2") (pin "32") (pinfunction "DB0_32") (pintype "bidirectional"))
    )
    (net (code "54") (name "unconnected-(X2-DB1-Pad31)") (class "Default")
      (node (ref "X2") (pin "31") (pinfunction "DB1_31") (pintype "bidirectional"))
    )
    (net (code "55") (name "unconnected-(X2-DB2-Pad30)") (class "Default")
      (node (ref "X2") (pin "30") (pinfunction "DB2_30") (pintype "bidirectional"))
    )
    (net (code "56") (name "unconnected-(X2-DB3-Pad29)") (class "Default")
      (node (ref "X2") (pin "29") (pinfunction "DB3_29") (pintype "bidirectional"))
    )
    (net (code "57") (name "unconnected-(X2-DB4-Pad28)") (class "Default")
      (node (ref "X2") (pin "28") (pinfunction "DB4_28") (pintype "bidirectional"))
    )
    (net (code "58") (name "unconnected-(X2-DB5-Pad27)") (class "Default")
      (node (ref "X2") (pin "27") (pinfunction "DB5_27") (pintype "bidirectional"))
    )
    (net (code "59") (name "unconnected-(X2-DB6-Pad26)") (class "Default")
      (node (ref "X2") (pin "26") (pinfunction "DB6_26") (pintype "bidirectional"))
    )
    (net (code "60") (name "unconnected-(X2-DB7-Pad25)") (class "Default")
      (node (ref "X2") (pin "25") (pinfunction "DB7_25") (pintype "bidirectional"))
    )
    (net (code "61") (name "unconnected-(X2-DB8-Pad24)") (class "Default")
      (node (ref "X2") (pin "24") (pinfunction "DB8_24") (pintype "bidirectional"))
    )
    (net (code "62") (name "unconnected-(X2-DB9-Pad23)") (class "Default")
      (node (ref "X2") (pin "23") (pinfunction "DB9_23") (pintype "bidirectional"))
    )
    (net (code "63") (name "unconnected-(X2-DB10-Pad22)") (class "Default")
      (node (ref "X2") (pin "22") (pinfunction "DB10_22") (pintype "bidirectional"))
    )
    (net (code "64") (name "unconnected-(X2-DB11-Pad21)") (class "Default")
      (node (ref "X2") (pin "21") (pinfunction "DB11_21") (pintype "bidirectional"))
    )
    (net (code "65") (name "unconnected-(X2-DB12-Pad20)") (class "Default")
      (node (ref "X2") (pin "20") (pinfunction "DB12_20") (pintype "bidirectional"))
    )
    (net (code "66") (name "unconnected-(X2-DB13-Pad19)") (class "Default")
      (node (ref "X2") (pin "19") (pinfunction "DB13_19") (pintype "bidirectional"))
    )
    (net (code "67") (name "unconnected-(X2-DB14-Pad18)") (class "Default")
      (node (ref "X2") (pin "18") (pinfunction "DB14_18") (pintype "bidirectional"))
    )
    (net (code "68") (name "unconnected-(X2-DB15-Pad17)") (class "Default")
      (node (ref "X2") (pin "17") (pinfunction "DB15_17") (pintype "bidirectional"))
    )
    (net (code "69") (name "unconnected-(X2-DB16-Pad16)") (class "Default")
      (node (ref "X2") (pin "16") (pinfunction "DB16_16") (pintype "bidirectional"))
    )
    (net (code "70") (name "unconnected-(X2-DB17-Pad15)") (class "Default")
      (node (ref "X2") (pin "15") (pinfunction "DB17_15") (pintype "bidirectional"))
    )
    (net (code "71") (name "unconnected-(X2-DE-Pad14)") (class "Default")
      (node (ref "X2") (pin "14") (pinfunction "DE_14") (pintype "bidirectional"))
    )
    (net (code "72") (name "unconnected-(X2-DOTCLK-Pad13)") (class "Default")
      (node (ref "X2") (pin "13") (pinfunction "DOTCLK_13") (pintype "bidirectional"))
    )
    (net (code "73") (name "unconnected-(X2-HSYNC-Pad12)") (class "Default")
      (node (ref "X2") (pin "12") (pinfunction "HSYNC_12") (pintype "bidirectional"))
    )
    (net (code "74") (name "unconnected-(X2-TE-Pad39)") (class "Default")
      (node (ref "X2") (pin "39") (pinfunction "TE_39") (pintype "bidirectional"))
    )
    (net (code "75") (name "unconnected-(X2-VSYNC-Pad11)") (class "Default")
      (node (ref "X2") (pin "11") (pinfunction "VSYNC_11") (pintype "bidirectional"))
    )
  )
)
